# first_schematic.net
KiCad netlist of a schematic drawn in EAGLE
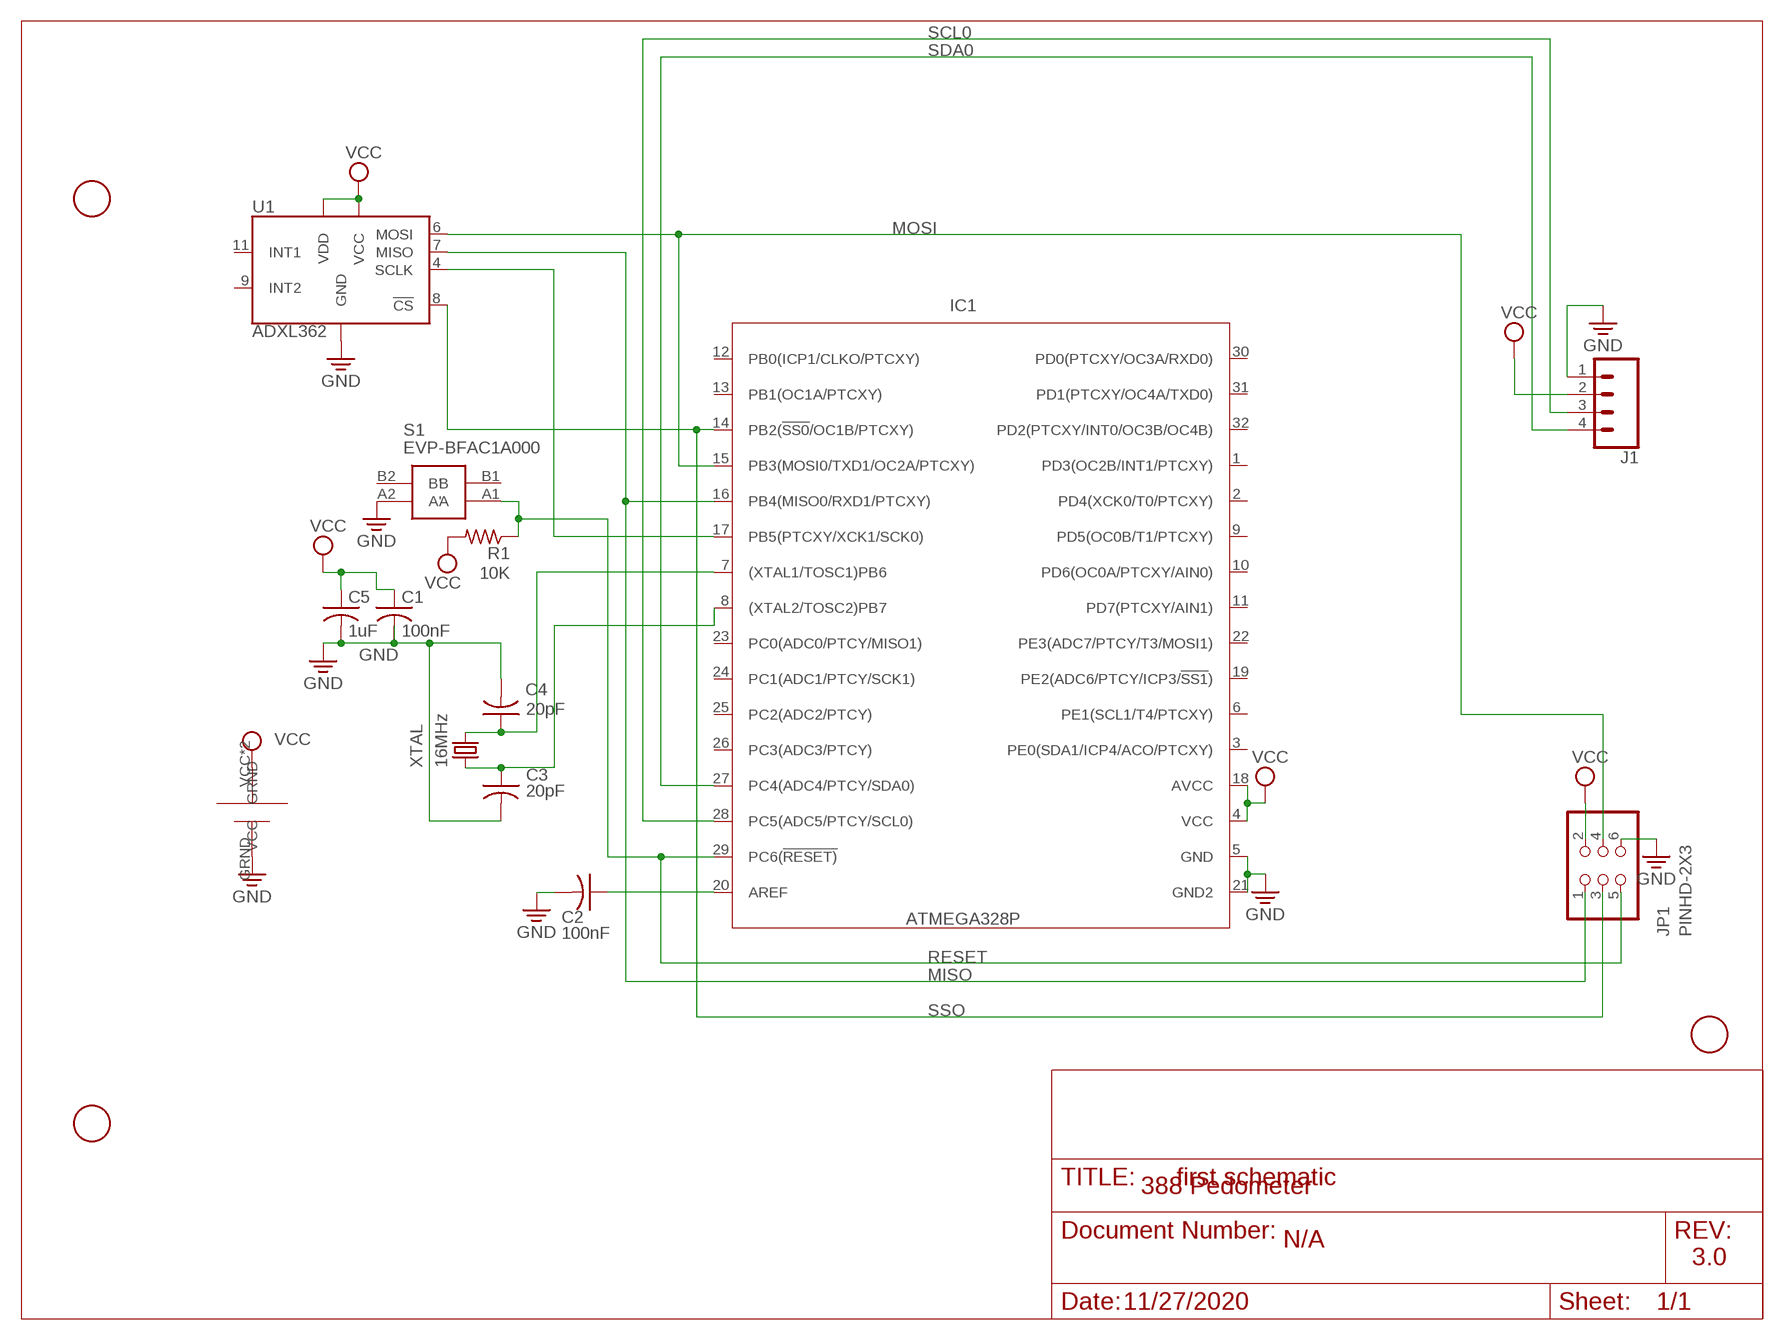
[diagram p0: schematic, sheet 1]

(export (version "E")
  (design (tool "Eeschema 10.0.6"))
  (components
    (comp (ref "C1")
      (value "100nF")
      (footprint "eagle-import:C0805")
      (libsource (lib "eagle-import") (part "C-USC0805"))
    )
    (comp (ref "C2")
      (value "100nF")
      (footprint "eagle-import:C0805")
      (libsource (lib "eagle-import") (part "C-USC0805"))
    )
    (comp (ref "C3")
      (value "20pF")
      (footprint "eagle-import:C0805")
      (libsource (lib "eagle-import") (part "C-USC0805"))
    )
    (comp (ref "C4")
      (value "20pF")
      (footprint "eagle-import:C0805")
      (libsource (lib "eagle-import") (part "C-USC0805"))
    )
    (comp (ref "C5")
      (value "1uF")
      (footprint "eagle-import:C0805")
      (libsource (lib "eagle-import") (part "C-USC0805"))
    )
    (comp (ref "IC1")
      (value "ATMEGA328P")
      (footprint "eagle-import:TQFP32-08")
      (fields (field (name "MANUFACTURER") "Microchip") (field (name "MPN") "ATMEGA328PB-AN"))
      (libsource (lib "eagle-import") (part "ATMEGA328PB_TQFP"))
    )
    (comp (ref "J1")
      (value "CONN_041X04_NO_SILK")
      (footprint "eagle-import:1X04_NO_SILK")
      (libsource (lib "eagle-import") (part "CONN_041X04_NO_SILK"))
    )
    (comp (ref "JP1")
      (value "PINHD-2X3")
      (footprint "eagle-import:2X03")
      (libsource (lib "eagle-import") (part "PINHD-2X3"))
    )
    (comp (ref "R1")
      (value "10K")
      (footprint "eagle-import:R0805")
      (libsource (lib "eagle-import") (part "R-US_R0805"))
    )
    (comp (ref "S1")
      (value "EVP-BFAC1A000")
      (footprint "eagle-import:EVPBFAC1A000")
      (fields (field (name "MF") "Panasonic Electronic"))
      (libsource (lib "eagle-import") (part "EVP-BFAC1A000"))
    )
    (comp (ref "U$1")
      (value "FIDUCIAL")
      (footprint "eagle-import:FIDUCIAL_1MM")
      (libsource (lib "eagle-import") (part "FIDUCIAL"))
    )
    (comp (ref "U$2")
      (value "FIDUCIAL")
      (footprint "eagle-import:FIDUCIAL_1MM")
      (libsource (lib "eagle-import") (part "FIDUCIAL"))
    )
    (comp (ref "U$3")
      (value "FIDUCIAL")
      (footprint "eagle-import:FIDUCIAL_1MM")
      (libsource (lib "eagle-import") (part "FIDUCIAL"))
    )
    (comp (ref "U$4")
      (value "CR2032")
      (footprint "eagle-import:CR2032")
      (libsource (lib "eagle-import") (part "CR2032"))
    )
    (comp (ref "U1")
      (value "ADXL362")
      (footprint "eagle-import:TFLGA-16_3.3MMX3.1MM")
      (fields (field (name "MF") "Analog Devices"))
      (libsource (lib "eagle-import") (part "ADXL362"))
    )
    (comp (ref "XTAL")
      (value "16MHz")
      (footprint "eagle-import:HC49UP")
      (libsource (lib "eagle-import") (part "CRYSTALHC49UP"))
    )
  )
  (nets
    (net (code "1") (name "/MISO") (class "Default")
      (node (ref "IC1") (pin "16") (pinfunction "PB4(MISO0/RXD1/PTCXY)_16") (pintype "bidirectional"))
      (node (ref "JP1") (pin "1") (pinfunction "1_1") (pintype "passive"))
      (node (ref "U1") (pin "7") (pinfunction "MISO_7") (pintype "bidirectional"))
    )
    (net (code "2") (name "/MOSI") (class "Default")
      (node (ref "IC1") (pin "15") (pinfunction "PB3(MOSI0/TXD1/OC2A/PTCXY)_15") (pintype "bidirectional"))
      (node (ref "JP1") (pin "4") (pinfunction "4_4") (pintype "passive"))
      (node (ref "U1") (pin "6") (pinfunction "MOSI_6") (pintype "bidirectional"))
    )
    (net (code "3") (name "/RESET") (class "Default")
      (node (ref "IC1") (pin "29") (pinfunction "PC6(~{RESET})_29") (pintype "bidirectional"))
      (node (ref "JP1") (pin "5") (pinfunction "5_5") (pintype "passive"))
      (node (ref "R1") (pin "1") (pinfunction "1_1") (pintype "passive"))
      (node (ref "S1") (pin "A1") (pinfunction "A_A1") (pintype "bidirectional"))
    )
    (net (code "4") (name "/SCL0") (class "Default")
      (node (ref "IC1") (pin "28") (pinfunction "PC5(ADC5/PTCY/SCL0)_28") (pintype "bidirectional"))
      (node (ref "J1") (pin "3") (pinfunction "3_3") (pintype "passive"))
    )
    (net (code "5") (name "/SDA0") (class "Default")
      (node (ref "IC1") (pin "27") (pinfunction "PC4(ADC4/PTCY/SDA0)_27") (pintype "bidirectional"))
      (node (ref "J1") (pin "4") (pinfunction "4_4") (pintype "passive"))
    )
    (net (code "6") (name "/SSO") (class "Default")
      (node (ref "IC1") (pin "14") (pinfunction "PB2(~{SS0}/OC1B/PTCXY)_14") (pintype "bidirectional"))
      (node (ref "JP1") (pin "3") (pinfunction "3_3") (pintype "passive"))
      (node (ref "U1") (pin "8") (pinfunction "~{CS}_8") (pintype "bidirectional"))
    )
    (net (code "7") (name "GND") (class "Default")
      (node (ref "C1") (pin "2") (pinfunction "2_2") (pintype "passive"))
      (node (ref "C2") (pin "2") (pinfunction "2_2") (pintype "passive"))
      (node (ref "C3") (pin "2") (pinfunction "2_2") (pintype "passive"))
      (node (ref "C4") (pin "2") (pinfunction "2_2") (pintype "passive"))
      (node (ref "C5") (pin "2") (pinfunction "2_2") (pintype "passive"))
      (node (ref "IC1") (pin "21") (pinfunction "GND2_21") (pintype "passive"))
      (node (ref "IC1") (pin "5") (pinfunction "GND_5") (pintype "passive"))
      (node (ref "J1") (pin "1") (pinfunction "1_1") (pintype "passive"))
      (node (ref "JP1") (pin "6") (pinfunction "6_6") (pintype "passive"))
      (node (ref "S1") (pin "A2") (pinfunction "A'_A2") (pintype "bidirectional"))
      (node (ref "U$4") (pin "GRND") (pinfunction "GRND_GRND") (pintype "bidirectional"))
      (node (ref "U1") (pin "12") (pinfunction "GND_12") (pintype "bidirectional"))
      (node (ref "U1") (pin "13") (pinfunction "GND_13") (pintype "bidirectional"))
      (node (ref "U1") (pin "16") (pinfunction "GND_16") (pintype "bidirectional"))
    )
    (net (code "8") (name "Net-(IC1-(XTAL1{slash}TOSC1)PB6)") (class "Default")
      (node (ref "C4") (pin "1") (pinfunction "1_1") (pintype "passive"))
      (node (ref "IC1") (pin "7") (pinfunction "(XTAL1/TOSC1)PB6_7") (pintype "bidirectional"))
      (node (ref "XTAL") (pin "2") (pinfunction "2_2") (pintype "passive"))
    )
    (net (code "9") (name "Net-(IC1-(XTAL2{slash}TOSC2)PB7)") (class "Default")
      (node (ref "C3") (pin "1") (pinfunction "1_1") (pintype "passive"))
      (node (ref "IC1") (pin "8") (pinfunction "(XTAL2/TOSC2)PB7_8") (pintype "bidirectional"))
      (node (ref "XTAL") (pin "1") (pinfunction "1_1") (pintype "passive"))
    )
    (net (code "10") (name "Net-(IC1-AREF)") (class "Default")
      (node (ref "C2") (pin "1") (pinfunction "1_1") (pintype "passive"))
      (node (ref "IC1") (pin "20") (pinfunction "AREF_20") (pintype "power_in"))
    )
    (net (code "11") (name "Net-(IC1-PB5(PTCXY{slash}XCK1{slash}SCK0))") (class "Default")
      (node (ref "IC1") (pin "17") (pinfunction "PB5(PTCXY/XCK1/SCK0)_17") (pintype "bidirectional"))
      (node (ref "U1") (pin "4") (pinfunction "SCLK_4") (pintype "bidirectional"))
    )
    (net (code "12") (name "VCC") (class "Default")
      (node (ref "C1") (pin "1") (pinfunction "1_1") (pintype "passive"))
      (node (ref "C5") (pin "1") (pinfunction "1_1") (pintype "passive"))
      (node (ref "IC1") (pin "18") (pinfunction "AVCC_18") (pintype "power_in"))
      (node (ref "IC1") (pin "4") (pinfunction "VCC_4") (pintype "power_in"))
      (node (ref "J1") (pin "2") (pinfunction "2_2") (pintype "passive"))
      (node (ref "JP1") (pin "2") (pinfunction "2_2") (pintype "passive"))
      (node (ref "R1") (pin "2") (pinfunction "2_2") (pintype "passive"))
      (node (ref "U$4") (pin "VCC") (pinfunction "VCC_VCC") (pintype "bidirectional"))
      (node (ref "U$4") (pin "VCC2") (pinfunction "VCC_VCC2") (pintype "bidirectional"))
      (node (ref "U1") (pin "1") (pinfunction "VDD_1") (pintype "bidirectional"))
      (node (ref "U1") (pin "14") (pinfunction "VCC_14") (pintype "bidirectional"))
    )
    (net (code "13") (name "unconnected-(IC1-PB0(ICP1{slash}CLKO{slash}PTCXY)-Pad12)") (class "Default")
      (node (ref "IC1") (pin "12") (pinfunction "PB0(ICP1/CLKO/PTCXY)_12") (pintype "bidirectional"))
    )
    (net (code "14") (name "unconnected-(IC1-PB1(OC1A{slash}PTCXY)-Pad13)") (class "Default")
      (node (ref "IC1") (pin "13") (pinfunction "PB1(OC1A/PTCXY)_13") (pintype "bidirectional"))
    )
    (net (code "15") (name "unconnected-(IC1-PC0(ADC0{slash}PTCY{slash}MISO1)-Pad23)") (class "Default")
      (node (ref "IC1") (pin "23") (pinfunction "PC0(ADC0/PTCY/MISO1)_23") (pintype "bidirectional"))
    )
    (net (code "16") (name "unconnected-(IC1-PC1(ADC1{slash}PTCY{slash}SCK1)-Pad24)") (class "Default")
      (node (ref "IC1") (pin "24") (pinfunction "PC1(ADC1/PTCY/SCK1)_24") (pintype "bidirectional"))
    )
    (net (code "17") (name "unconnected-(IC1-PC2(ADC2{slash}PTCY)-Pad25)") (class "Default")
      (node (ref "IC1") (pin "25") (pinfunction "PC2(ADC2/PTCY)_25") (pintype "bidirectional"))
    )
    (net (code "18") (name "unconnected-(IC1-PC3(ADC3{slash}PTCY)-Pad26)") (class "Default")
      (node (ref "IC1") (pin "26") (pinfunction "PC3(ADC3/PTCY)_26") (pintype "bidirectional"))
    )
    (net (code "19") (name "unconnected-(IC1-PD0(PTCXY{slash}OC3A{slash}RXD0)-Pad30)") (class "Default")
      (node (ref "IC1") (pin "30") (pinfunction "PD0(PTCXY/OC3A/RXD0)_30") (pintype "bidirectional"))
    )
    (net (code "20") (name "unconnected-(IC1-PD1(PTCXY{slash}OC4A{slash}TXD0)-Pad31)") (class "Default")
      (node (ref "IC1") (pin "31") (pinfunction "PD1(PTCXY/OC4A/TXD0)_31") (pintype "bidirectional"))
    )
    (net (code "21") (name "unconnected-(IC1-PD2(PTCXY{slash}INT0{slash}OC3B{slash}OC4B)-Pad32)") (class "Default")
      (node (ref "IC1") (pin "32") (pinfunction "PD2(PTCXY/INT0/OC3B/OC4B)_32") (pintype "bidirectional"))
    )
    (net (code "22") (name "unconnected-(IC1-PD3(OC2B{slash}INT1{slash}PTCXY)-Pad1)") (class "Default")
      (node (ref "IC1") (pin "1") (pinfunction "PD3(OC2B/INT1/PTCXY)_1") (pintype "bidirectional"))
    )
    (net (code "23") (name "unconnected-(IC1-PD4(XCK0{slash}T0{slash}PTCXY)-Pad2)") (class "Default")
      (node (ref "IC1") (pin "2") (pinfunction "PD4(XCK0/T0/PTCXY)_2") (pintype "bidirectional"))
    )
    (net (code "24") (name "unconnected-(IC1-PD5(OC0B{slash}T1{slash}PTCXY)-Pad9)") (class "Default")
      (node (ref "IC1") (pin "9") (pinfunction "PD5(OC0B/T1/PTCXY)_9") (pintype "bidirectional"))
    )
    (net (code "25") (name "unconnected-(IC1-PD6(OC0A{slash}PTCXY{slash}AIN0)-Pad10)") (class "Default")
      (node (ref "IC1") (pin "10") (pinfunction "PD6(OC0A/PTCXY/AIN0)_10") (pintype "bidirectional"))
    )
    (net (code "26") (name "unconnected-(IC1-PD7(PTCXY{slash}AIN1)-Pad11)") (class "Default")
      (node (ref "IC1") (pin "11") (pinfunction "PD7(PTCXY/AIN1)_11") (pintype "bidirectional"))
    )
    (net (code "27") (name "unconnected-(IC1-PE0(SDA1{slash}ICP4{slash}ACO{slash}PTCXY)-Pad3)") (class "Default")
      (node (ref "IC1") (pin "3") (pinfunction "PE0(SDA1/ICP4/ACO/PTCXY)_3") (pintype "bidirectional"))
    )
    (net (code "28") (name "unconnected-(IC1-PE1(SCL1{slash}T4{slash}PTCXY)-Pad6)") (class "Default")
      (node (ref "IC1") (pin "6") (pinfunction "PE1(SCL1/T4/PTCXY)_6") (pintype "bidirectional"))
    )
    (net (code "29") (name "unconnected-(IC1-PE2(ADC6{slash}PTCY{slash}ICP3{slash}~{SS1})-Pad19)") (class "Default")
      (node (ref "IC1") (pin "19") (pinfunction "PE2(ADC6/PTCY/ICP3/~{SS1})_19") (pintype "bidirectional"))
    )
    (net (code "30") (name "unconnected-(IC1-PE3(ADC7{slash}PTCY{slash}T3{slash}MOSI1)-Pad22)") (class "Default")
      (node (ref "IC1") (pin "22") (pinfunction "PE3(ADC7/PTCY/T3/MOSI1)_22") (pintype "bidirectional"))
    )
    (net (code "31") (name "unconnected-(S1-B'-PadB2)") (class "Default")
      (node (ref "S1") (pin "B2") (pinfunction "B'_B2") (pintype "bidirectional"))
    )
    (net (code "32") (name "unconnected-(S1-B-PadB1)") (class "Default")
      (node (ref "S1") (pin "B1") (pinfunction "B_B1") (pintype "bidirectional"))
    )
    (net (code "33") (name "unconnected-(U1-INT1-Pad11)") (class "Default")
      (node (ref "U1") (pin "11") (pinfunction "INT1_11") (pintype "bidirectional"))
    )
    (net (code "34") (name "unconnected-(U1-INT2-Pad9)") (class "Default")
      (node (ref "U1") (pin "9") (pinfunction "INT2_9") (pintype "bidirectional"))
    )
  )
)
